# Pure_LFO.net
KiCad netlist of a schematic drawn in EAGLE
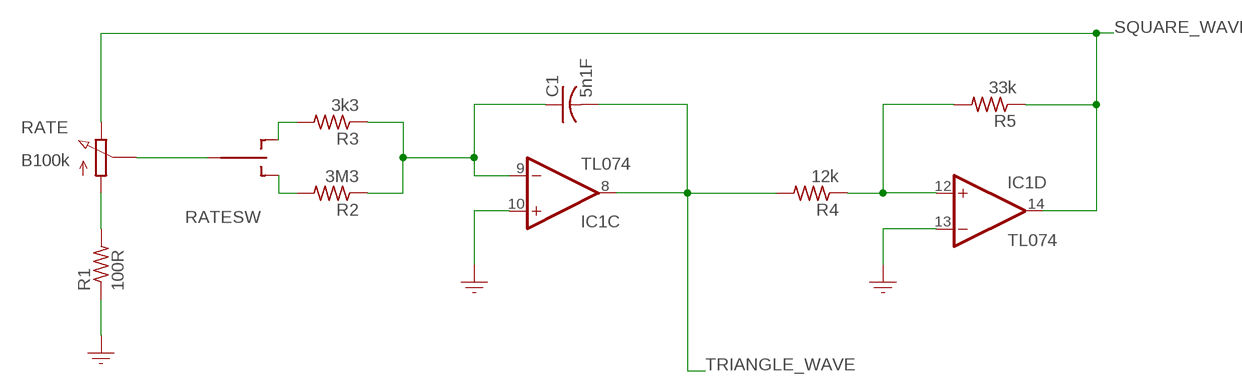
[diagram p0: schematic, sheet 1]
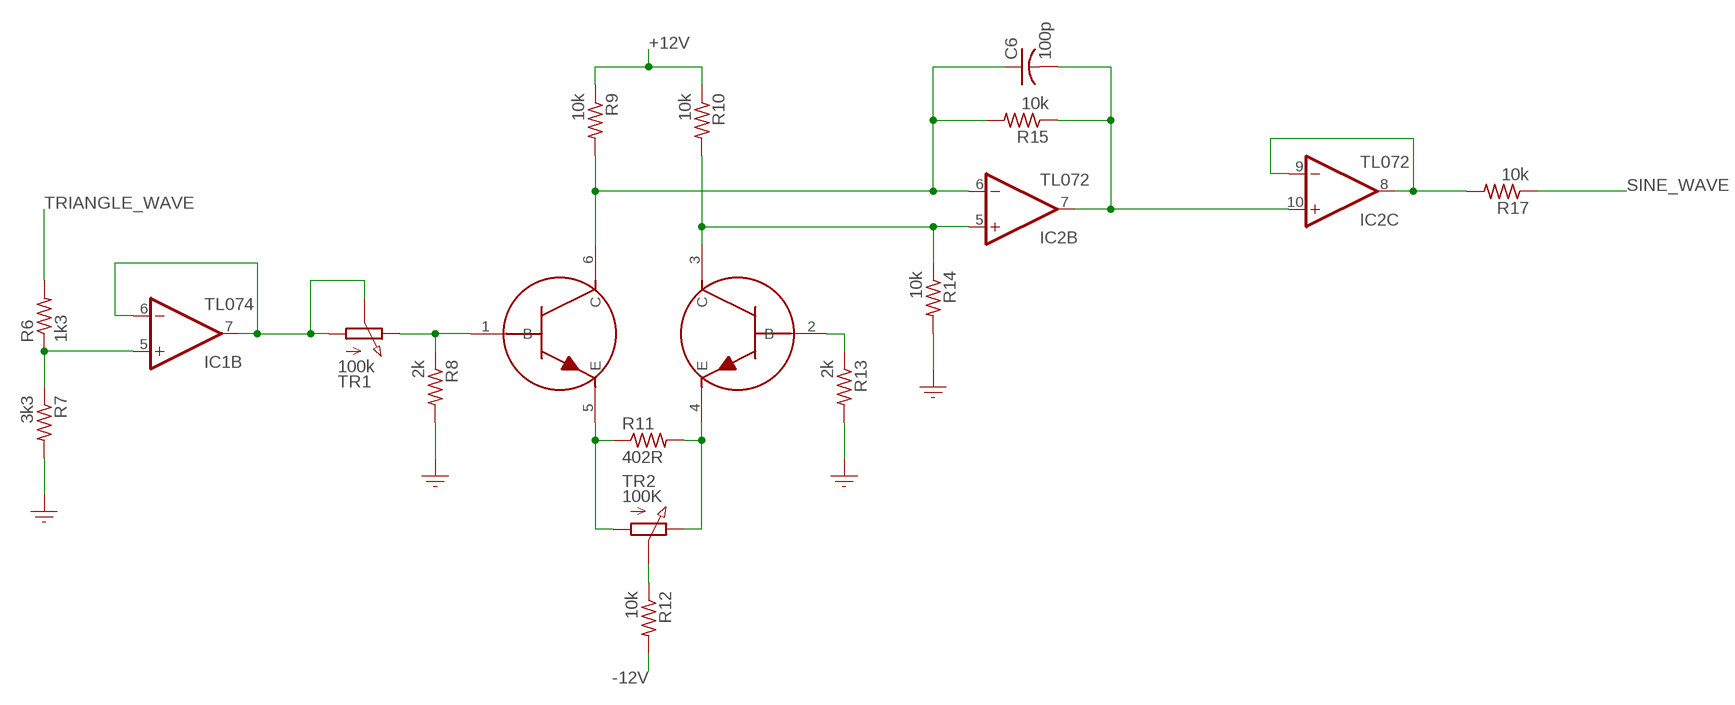
[diagram p1: schematic, sheet 2]
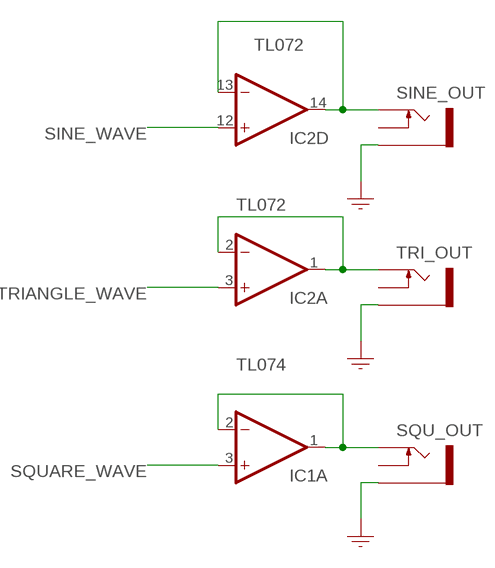
[diagram p2: schematic, sheet 3]
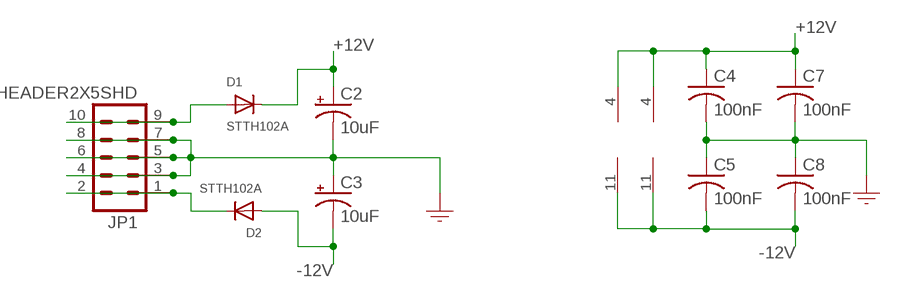
[diagram p3: schematic, sheet 4]

(export (version "E")
  (design (tool "Eeschema 10.0.6"))
  (components
    (comp (ref "C6")
      (value "100p")
      (footprint "eagle-import:C0805")
      (libsource (lib "eagle-import") (part "CAPACITOR-USC0805"))
    )
    (comp (ref "IC1")
      (value "TL074")
      (footprint "eagle-import:SO14")
      (libsource (lib "eagle-import") (part "OPAMP_QUADD"))
    )
    (comp (ref "IC2")
      (value "TL072")
      (footprint "eagle-import:SO14")
      (libsource (lib "eagle-import") (part "OPAMP_QUADD"))
    )
    (comp (ref "R6")
      (value "1k3")
      (footprint "eagle-import:R0805")
      (libsource (lib "eagle-import") (part "RESISTOR_USR0805"))
    )
    (comp (ref "R7")
      (value "3k3")
      (footprint "eagle-import:R0805")
      (libsource (lib "eagle-import") (part "RESISTOR_USR0805"))
    )
    (comp (ref "R8")
      (value "2k")
      (footprint "eagle-import:R0805")
      (libsource (lib "eagle-import") (part "RESISTOR_USR0805"))
    )
    (comp (ref "R9")
      (value "10k")
      (footprint "eagle-import:R0805")
      (libsource (lib "eagle-import") (part "RESISTOR_USR0805"))
    )
    (comp (ref "R10")
      (value "10k")
      (footprint "eagle-import:R0805")
      (libsource (lib "eagle-import") (part "RESISTOR_USR0805"))
    )
    (comp (ref "R11")
      (value "402R")
      (footprint "eagle-import:R0805")
      (libsource (lib "eagle-import") (part "RESISTOR_USR0805"))
    )
    (comp (ref "R12")
      (value "10k")
      (footprint "eagle-import:R0805")
      (libsource (lib "eagle-import") (part "RESISTOR_USR0805"))
    )
    (comp (ref "R13")
      (value "2k")
      (footprint "eagle-import:R0805")
      (libsource (lib "eagle-import") (part "RESISTOR_USR0805"))
    )
    (comp (ref "R14")
      (value "10k")
      (footprint "eagle-import:R0805")
      (libsource (lib "eagle-import") (part "RESISTOR_USR0805"))
    )
    (comp (ref "R15")
      (value "10k")
      (footprint "eagle-import:R0805")
      (libsource (lib "eagle-import") (part "RESISTOR_USR0805"))
    )
    (comp (ref "R17")
      (value "10k")
      (footprint "eagle-import:R0805")
      (libsource (lib "eagle-import") (part "RESISTOR_USR0805"))
    )
    (comp (ref "T3")
      (value "DMMT3904W-7-F")
      (footprint "eagle-import:TRANS_PAIR")
      (libsource (lib "eagle-import") (part "TRANSISTOR_PAIR_NPN"))
    )
    (comp (ref "TR1")
      (value "100k")
      (footprint "eagle-import:TRIMMER_TH")
      (libsource (lib "eagle-import") (part "RESISTOR_VARIABLETRIMMER_TH"))
    )
    (comp (ref "TR2")
      (value "100K")
      (footprint "eagle-import:TRIMMER_TH")
      (libsource (lib "eagle-import") (part "RESISTOR_VARIABLETRIMMER_TH"))
    )
    (comp (ref "SINE_OUT")
      (value "SOCKET_MONO_3.5MMPJ301M-12")
      (footprint "eagle-import:PJ301M-12")
      (libsource (lib "eagle-import") (part "SOCKET_MONO_3.5MMPJ301M-12"))
    )
    (comp (ref "SQU_OUT")
      (value "SOCKET_MONO_3.5MMPJ301M-12")
      (footprint "eagle-import:PJ301M-12")
      (libsource (lib "eagle-import") (part "SOCKET_MONO_3.5MMPJ301M-12"))
    )
    (comp (ref "TRI_OUT")
      (value "SOCKET_MONO_3.5MMPJ301M-12")
      (footprint "eagle-import:PJ301M-12")
      (libsource (lib "eagle-import") (part "SOCKET_MONO_3.5MMPJ301M-12"))
    )
    (comp (ref "C1")
      (value "5n1F")
      (footprint "eagle-import:C0805")
      (libsource (lib "eagle-import") (part "CAPACITOR-USC0805"))
    )
    (comp (ref "R1")
      (value "100R")
      (footprint "eagle-import:R0805")
      (libsource (lib "eagle-import") (part "RESISTOR_USR0805"))
    )
    (comp (ref "R2")
      (value "3M3")
      (footprint "eagle-import:R0805")
      (libsource (lib "eagle-import") (part "RESISTOR_USR0805"))
    )
    (comp (ref "R3")
      (value "3k3")
      (footprint "eagle-import:R0805")
      (libsource (lib "eagle-import") (part "RESISTOR_USR0805"))
    )
    (comp (ref "R4")
      (value "12k")
      (footprint "eagle-import:R0805")
      (libsource (lib "eagle-import") (part "RESISTOR_USR0805"))
    )
    (comp (ref "R5")
      (value "33k")
      (footprint "eagle-import:R0805")
      (libsource (lib "eagle-import") (part "RESISTOR_USR0805"))
    )
    (comp (ref "RATE")
      (value "B100k")
      (footprint "eagle-import:POTENTIOMETER_9MM")
      (libsource (lib "eagle-import") (part "RESISTOR_VARIABLE9MM_POT"))
    )
    (comp (ref "RATESW")
      (value "SWITCH_TOGGLE_SPDT")
      (footprint "eagle-import:TOGGLE_SW")
      (libsource (lib "eagle-import") (part "SWITCH_TOGGLE_SPDT"))
    )
    (comp (ref "C2")
      (value "10uF")
      (footprint "eagle-import:153CLV-0505")
      (libsource (lib "eagle-import") (part "CAPACITOR_POL-US153CLV-0505"))
    )
    (comp (ref "C3")
      (value "10uF")
      (footprint "eagle-import:153CLV-0505")
      (libsource (lib "eagle-import") (part "CAPACITOR_POL-US153CLV-0505"))
    )
    (comp (ref "C4")
      (value "100nF")
      (footprint "eagle-import:C0805")
      (libsource (lib "eagle-import") (part "CAPACITOR-USC0805"))
    )
    (comp (ref "C5")
      (value "100nF")
      (footprint "eagle-import:C0805")
      (libsource (lib "eagle-import") (part "CAPACITOR-USC0805"))
    )
    (comp (ref "C7")
      (value "100nF")
      (footprint "eagle-import:C0805")
      (libsource (lib "eagle-import") (part "CAPACITOR-USC0805"))
    )
    (comp (ref "C8")
      (value "100nF")
      (footprint "eagle-import:C0805")
      (libsource (lib "eagle-import") (part "CAPACITOR-USC0805"))
    )
    (comp (ref "D1")
      (value "STTH102A")
      (footprint "eagle-import:SMADIODE")
      (libsource (lib "eagle-import") (part "DIODESMA"))
    )
    (comp (ref "D2")
      (value "STTH102A")
      (footprint "eagle-import:SMADIODE")
      (libsource (lib "eagle-import") (part "DIODESMA"))
    )
    (comp (ref "JP1")
      (value "HEADER2X5SHD")
      (footprint "eagle-import:2X5-SHROUDED")
      (libsource (lib "eagle-import") (part "HEADER2X5SHD"))
    )
  )
  (nets
    (net (code "1") (name "+12V") (class "Default")
      (node (ref "C2") (pin "+") (pinfunction "+_+") (pintype "passive"))
      (node (ref "C4") (pin "1") (pinfunction "1_1") (pintype "passive"))
      (node (ref "C7") (pin "1") (pinfunction "1_1") (pintype "passive"))
      (node (ref "D1") (pin "C") (pinfunction "C_C") (pintype "passive"))
      (node (ref "IC1") (pin "4") (pinfunction "V+_4") (pintype "power_in"))
      (node (ref "IC2") (pin "4") (pinfunction "V+_4") (pintype "power_in"))
      (node (ref "R10") (pin "1") (pinfunction "1_1") (pintype "passive"))
      (node (ref "R9") (pin "1") (pinfunction "1_1") (pintype "passive"))
    )
    (net (code "2") (name "-12V") (class "Default")
      (node (ref "C3") (pin "-") (pinfunction "-_-") (pintype "passive"))
      (node (ref "C5") (pin "2") (pinfunction "2_2") (pintype "passive"))
      (node (ref "C8") (pin "2") (pinfunction "2_2") (pintype "passive"))
      (node (ref "D2") (pin "A") (pinfunction "A_A") (pintype "passive"))
      (node (ref "IC1") (pin "11") (pinfunction "V-_11") (pintype "power_in"))
      (node (ref "IC2") (pin "11") (pinfunction "V-_11") (pintype "power_in"))
      (node (ref "R12") (pin "2") (pinfunction "2_2") (pintype "passive"))
    )
    (net (code "3") (name "GND") (class "Default")
      (node (ref "C2") (pin "-") (pinfunction "-_-") (pintype "passive"))
      (node (ref "C3") (pin "+") (pinfunction "+_+") (pintype "passive"))
      (node (ref "C4") (pin "2") (pinfunction "2_2") (pintype "passive"))
      (node (ref "C5") (pin "1") (pinfunction "1_1") (pintype "passive"))
      (node (ref "C7") (pin "2") (pinfunction "2_2") (pintype "passive"))
      (node (ref "C8") (pin "1") (pinfunction "1_1") (pintype "passive"))
      (node (ref "IC1") (pin "10") (pinfunction "+IN_10") (pintype "input"))
      (node (ref "IC1") (pin "13") (pinfunction "-IN_13") (pintype "input"))
      (node (ref "JP1") (pin "3") (pinfunction "3_3") (pintype "passive"))
      (node (ref "JP1") (pin "4") (pinfunction "4_4") (pintype "passive"))
      (node (ref "JP1") (pin "5") (pinfunction "5_5") (pintype "passive"))
      (node (ref "JP1") (pin "6") (pinfunction "6_6") (pintype "passive"))
      (node (ref "JP1") (pin "7") (pinfunction "7_7") (pintype "passive"))
      (node (ref "JP1") (pin "8") (pinfunction "8_8") (pintype "passive"))
      (node (ref "R1") (pin "1") (pinfunction "1_1") (pintype "passive"))
      (node (ref "R13") (pin "2") (pinfunction "2_2") (pintype "passive"))
      (node (ref "R14") (pin "2") (pinfunction "2_2") (pintype "passive"))
      (node (ref "R7") (pin "2") (pinfunction "2_2") (pintype "passive"))
      (node (ref "R8") (pin "2") (pinfunction "2_2") (pintype "passive"))
      (node (ref "SINE_OUT") (pin "GND") (pinfunction "SLEEVE_GND") (pintype "passive"))
      (node (ref "SQU_OUT") (pin "GND") (pinfunction "SLEEVE_GND") (pintype "passive"))
      (node (ref "TRI_OUT") (pin "GND") (pinfunction "SLEEVE_GND") (pintype "passive"))
    )
    (net (code "4") (name "Net-(D1-PadA)") (class "Default")
      (node (ref "D1") (pin "A") (pinfunction "A_A") (pintype "passive"))
      (node (ref "JP1") (pin "10") (pinfunction "10_10") (pintype "passive"))
      (node (ref "JP1") (pin "9") (pinfunction "9_9") (pintype "passive"))
    )
    (net (code "5") (name "Net-(D2-PadC)") (class "Default")
      (node (ref "D2") (pin "C") (pinfunction "C_C") (pintype "passive"))
      (node (ref "JP1") (pin "1") (pinfunction "1_1") (pintype "passive"))
      (node (ref "JP1") (pin "2") (pinfunction "2_2") (pintype "passive"))
    )
    (net (code "6") (name "Net-(IC1A--IN)") (class "Default")
      (node (ref "IC1") (pin "1") (pinfunction "OUT_1") (pintype "output"))
      (node (ref "IC1") (pin "2") (pinfunction "-IN_2") (pintype "input"))
      (node (ref "SQU_OUT") (pin "TIP") (pinfunction "TIP_TIP") (pintype "passive"))
    )
    (net (code "7") (name "Net-(IC1B-+IN)") (class "Default")
      (node (ref "IC1") (pin "5") (pinfunction "+IN_5") (pintype "input"))
      (node (ref "R6") (pin "1") (pinfunction "1_1") (pintype "passive"))
      (node (ref "R7") (pin "1") (pinfunction "1_1") (pintype "passive"))
    )
    (net (code "8") (name "Net-(IC1B--IN)") (class "Default")
      (node (ref "IC1") (pin "6") (pinfunction "-IN_6") (pintype "input"))
      (node (ref "IC1") (pin "7") (pinfunction "OUT_7") (pintype "output"))
      (node (ref "TR1") (pin "1") (pinfunction "1_1") (pintype "passive"))
      (node (ref "TR1") (pin "2") (pinfunction "2_2") (pintype "passive"))
    )
    (net (code "9") (name "Net-(IC1C--IN)") (class "Default")
      (node (ref "C1") (pin "1") (pinfunction "1_1") (pintype "passive"))
      (node (ref "IC1") (pin "9") (pinfunction "-IN_9") (pintype "input"))
      (node (ref "R2") (pin "1") (pinfunction "1_1") (pintype "passive"))
      (node (ref "R3") (pin "1") (pinfunction "1_1") (pintype "passive"))
    )
    (net (code "10") (name "Net-(IC1D-+IN)") (class "Default")
      (node (ref "IC1") (pin "12") (pinfunction "+IN_12") (pintype "input"))
      (node (ref "R4") (pin "1") (pinfunction "1_1") (pintype "passive"))
      (node (ref "R5") (pin "2") (pinfunction "2_2") (pintype "passive"))
    )
    (net (code "11") (name "Net-(IC2A--IN)") (class "Default")
      (node (ref "IC2") (pin "1") (pinfunction "OUT_1") (pintype "output"))
      (node (ref "IC2") (pin "2") (pinfunction "-IN_2") (pintype "input"))
      (node (ref "TRI_OUT") (pin "TIP") (pinfunction "TIP_TIP") (pintype "passive"))
    )
    (net (code "12") (name "Net-(IC2B-+IN)") (class "Default")
      (node (ref "IC2") (pin "5") (pinfunction "+IN_5") (pintype "input"))
      (node (ref "R10") (pin "2") (pinfunction "2_2") (pintype "passive"))
      (node (ref "R14") (pin "1") (pinfunction "1_1") (pintype "passive"))
      (node (ref "T3") (pin "3") (pinfunction "C_3") (pintype "bidirectional"))
    )
    (net (code "13") (name "Net-(IC2B--IN)") (class "Default")
      (node (ref "C6") (pin "1") (pinfunction "1_1") (pintype "passive"))
      (node (ref "IC2") (pin "6") (pinfunction "-IN_6") (pintype "input"))
      (node (ref "R15") (pin "2") (pinfunction "2_2") (pintype "passive"))
      (node (ref "R9") (pin "2") (pinfunction "2_2") (pintype "passive"))
      (node (ref "T3") (pin "6") (pinfunction "C_6") (pintype "bidirectional"))
    )
    (net (code "14") (name "Net-(IC2B-OUT)") (class "Default")
      (node (ref "C6") (pin "2") (pinfunction "2_2") (pintype "passive"))
      (node (ref "IC2") (pin "10") (pinfunction "+IN_10") (pintype "input"))
      (node (ref "IC2") (pin "7") (pinfunction "OUT_7") (pintype "output"))
      (node (ref "R15") (pin "1") (pinfunction "1_1") (pintype "passive"))
    )
    (net (code "15") (name "Net-(IC2C--IN)") (class "Default")
      (node (ref "IC2") (pin "8") (pinfunction "OUT_8") (pintype "output"))
      (node (ref "IC2") (pin "9") (pinfunction "-IN_9") (pintype "input"))
      (node (ref "R17") (pin "2") (pinfunction "2_2") (pintype "passive"))
    )
    (net (code "16") (name "Net-(IC2D--IN)") (class "Default")
      (node (ref "IC2") (pin "13") (pinfunction "-IN_13") (pintype "input"))
      (node (ref "IC2") (pin "14") (pinfunction "OUT_14") (pintype "output"))
      (node (ref "SINE_OUT") (pin "TIP") (pinfunction "TIP_TIP") (pintype "passive"))
    )
    (net (code "17") (name "Net-(R12-Pad1)") (class "Default")
      (node (ref "R12") (pin "1") (pinfunction "1_1") (pintype "passive"))
      (node (ref "TR2") (pin "2") (pinfunction "2_2") (pintype "passive"))
    )
    (net (code "18") (name "Net-(RATE-1)") (class "Default")
      (node (ref "R1") (pin "2") (pinfunction "2_2") (pintype "passive"))
      (node (ref "RATE") (pin "P$1") (pinfunction "1_P$1") (pintype "passive"))
    )
    (net (code "19") (name "Net-(RATE-2)") (class "Default")
      (node (ref "RATE") (pin "P$2") (pinfunction "2_P$2") (pintype "passive"))
      (node (ref "RATESW") (pin "2") (pinfunction "P_2") (pintype "passive"))
    )
    (net (code "20") (name "Net-(RATESW-O)") (class "Default")
      (node (ref "R3") (pin "2") (pinfunction "2_2") (pintype "passive"))
      (node (ref "RATESW") (pin "1") (pinfunction "O_1") (pintype "passive"))
    )
    (net (code "21") (name "Net-(RATESW-S)") (class "Default")
      (node (ref "R2") (pin "2") (pinfunction "2_2") (pintype "passive"))
      (node (ref "RATESW") (pin "3") (pinfunction "S_3") (pintype "passive"))
    )
    (net (code "22") (name "Net-(T3A-B)") (class "Default")
      (node (ref "R13") (pin "1") (pinfunction "1_1") (pintype "passive"))
      (node (ref "T3") (pin "2") (pinfunction "B_2") (pintype "bidirectional"))
    )
    (net (code "23") (name "Net-(T3A-E)") (class "Default")
      (node (ref "R11") (pin "2") (pinfunction "2_2") (pintype "passive"))
      (node (ref "T3") (pin "4") (pinfunction "E_4") (pintype "bidirectional"))
      (node (ref "TR2") (pin "3") (pinfunction "3_3") (pintype "passive"))
    )
    (net (code "24") (name "Net-(T3B-B)") (class "Default")
      (node (ref "R8") (pin "1") (pinfunction "1_1") (pintype "passive"))
      (node (ref "T3") (pin "1") (pinfunction "B_1") (pintype "bidirectional"))
      (node (ref "TR1") (pin "3") (pinfunction "3_3") (pintype "passive"))
    )
    (net (code "25") (name "Net-(T3B-E)") (class "Default")
      (node (ref "R11") (pin "1") (pinfunction "1_1") (pintype "passive"))
      (node (ref "T3") (pin "5") (pinfunction "E_5") (pintype "bidirectional"))
      (node (ref "TR2") (pin "1") (pinfunction "1_1") (pintype "passive"))
    )
    (net (code "26") (name "SINE_WAVE") (class "Default")
      (node (ref "IC2") (pin "12") (pinfunction "+IN_12") (pintype "input"))
      (node (ref "R17") (pin "1") (pinfunction "1_1") (pintype "passive"))
    )
    (net (code "27") (name "SQUARE_WAVE") (class "Default")
      (node (ref "IC1") (pin "14") (pinfunction "OUT_14") (pintype "output"))
      (node (ref "IC1") (pin "3") (pinfunction "+IN_3") (pintype "input"))
      (node (ref "R5") (pin "1") (pinfunction "1_1") (pintype "passive"))
      (node (ref "RATE") (pin "P$3") (pinfunction "3_P$3") (pintype "passive"))
    )
    (net (code "28") (name "TRIANGLE_WAVE") (class "Default")
      (node (ref "C1") (pin "2") (pinfunction "2_2") (pintype "passive"))
      (node (ref "IC1") (pin "8") (pinfunction "OUT_8") (pintype "output"))
      (node (ref "IC2") (pin "3") (pinfunction "+IN_3") (pintype "input"))
      (node (ref "R4") (pin "2") (pinfunction "2_2") (pintype "passive"))
      (node (ref "R6") (pin "2") (pinfunction "2_2") (pintype "passive"))
    )
    (net (code "29") (name "unconnected-(SINE_OUT-SWITCH-PadNORM)") (class "Default")
      (node (ref "SINE_OUT") (pin "NORM") (pinfunction "SWITCH_NORM") (pintype "passive"))
    )
    (net (code "30") (name "unconnected-(SQU_OUT-SWITCH-PadNORM)") (class "Default")
      (node (ref "SQU_OUT") (pin "NORM") (pinfunction "SWITCH_NORM") (pintype "passive"))
    )
    (net (code "31") (name "unconnected-(TRI_OUT-SWITCH-PadNORM)") (class "Default")
      (node (ref "TRI_OUT") (pin "NORM") (pinfunction "SWITCH_NORM") (pintype "passive"))
    )
  )
)
